# Input_Digital.net
KiCad netlist of a schematic drawn in Altium Designer
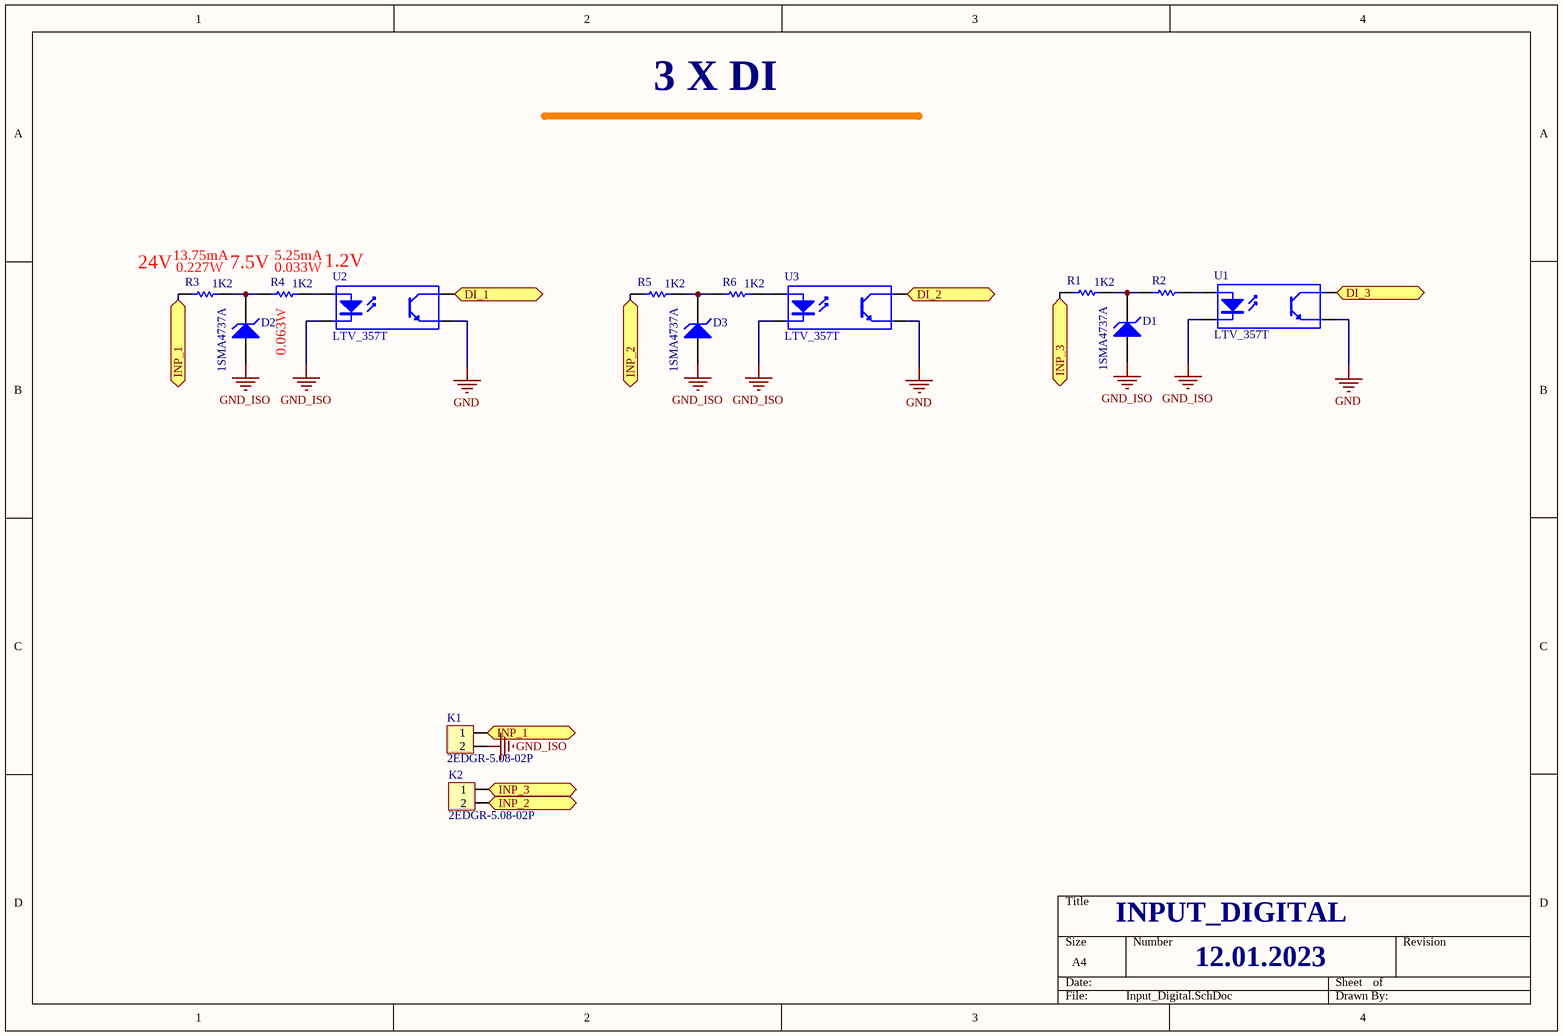
[diagram p0: Input_Digital.SchDoc]

(export (version "E")
  (design (tool "Eeschema 10.0.6"))
  (components
    (comp (ref "D1")
      (value "1SMA4737A")
      (footprint "DO214AC")
      (description "DIODE Zener Diode 7.5V 1W DO214AC")
      (fields (field (name "PUBLISHER") "Altium Limited"))
      (libsource (lib "geolib") (part "DIODE"))
    )
    (comp (ref "D2")
      (value "1SMA4737A")
      (footprint "DO214AC")
      (description "DIODE Zener Diode 7.5V 1W DO214AC")
      (fields (field (name "PUBLISHER") "Altium Limited"))
      (libsource (lib "geolib") (part "DIODE"))
    )
    (comp (ref "D3")
      (value "1SMA4737A")
      (footprint "DO214AC")
      (description "DIODE Zener Diode 7.5V 1W DO214AC")
      (fields (field (name "PUBLISHER") "Altium Limited"))
      (libsource (lib "geolib") (part "DIODE"))
    )
    (comp (ref "K1")
      (value "2EDGR-5.08-02P")
      (footprint "CON_DG129_02P")
      (description "CONNECTOR 5.08mm 2PIN 90DEG")
      (libsource (lib "geolib") (part "KLEMENS_2P"))
    )
    (comp (ref "K2")
      (value "2EDGR-5.08-02P")
      (footprint "CON_DG129_02P")
      (description "CONNECTOR 5.08mm 2PIN 90DEG")
      (libsource (lib "geolib") (part "KLEMENS_2P"))
    )
    (comp (ref "R1")
      (value "1K2")
      (footprint "RES3216[1206]")
      (description "RESISTOR 1206 Case %1")
      (fields (field (name "PUBLISHER") "Altium Limited"))
      (libsource (lib "geolib") (part "RES"))
    )
    (comp (ref "R2")
      (value "1K2")
      (footprint "RES2012[0805]")
      (description "RESISTOR 0805 Case %1")
      (fields (field (name "PUBLISHER") "Altium Limited"))
      (libsource (lib "geolib") (part "RES"))
    )
    (comp (ref "R3")
      (value "1K2")
      (footprint "RES3216[1206]")
      (description "RESISTOR 1206 Case %1")
      (fields (field (name "PUBLISHER") "Altium Limited"))
      (libsource (lib "geolib") (part "RES"))
    )
    (comp (ref "R4")
      (value "1K2")
      (footprint "RES2012[0805]")
      (description "RESISTOR 0805 Case %1")
      (fields (field (name "PUBLISHER") "Altium Limited"))
      (libsource (lib "geolib") (part "RES"))
    )
    (comp (ref "R5")
      (value "1K2")
      (footprint "RES3216[1206]")
      (description "RESISTOR 1206 Case %1")
      (fields (field (name "PUBLISHER") "Altium Limited"))
      (libsource (lib "geolib") (part "RES"))
    )
    (comp (ref "R6")
      (value "1K2")
      (footprint "RES2012[0805]")
      (description "RESISTOR 0805 Case %1")
      (fields (field (name "PUBLISHER") "Altium Limited"))
      (libsource (lib "geolib") (part "RES"))
    )
    (comp (ref "U1")
      (value "LTV_357T")
      (footprint "SMD-4")
      (description "OPTOCOUPLER Transistor Output Optocouplers Optocoupler Phototrans")
      (fields (field (name "PUBLISHER") "Altium Limited"))
      (libsource (lib "geolib") (part "LVT_357T"))
    )
    (comp (ref "U2")
      (value "LTV_357T")
      (footprint "SMD-4")
      (description "OPTOCOUPLER Transistor Output Optocouplers Optocoupler Phototrans")
      (fields (field (name "PUBLISHER") "Altium Limited"))
      (libsource (lib "geolib") (part "LVT_357T"))
    )
    (comp (ref "U3")
      (value "LTV_357T")
      (footprint "SMD-4")
      (description "OPTOCOUPLER Transistor Output Optocouplers Optocoupler Phototrans")
      (fields (field (name "PUBLISHER") "Altium Limited"))
      (libsource (lib "geolib") (part "LVT_357T"))
    )
  )
  (nets
    (net (code "1") (name "/DI_1") (class "Default")
      (node (ref "U2") (pin "4") (pinfunction "C_4") (pintype "passive"))
    )
    (net (code "2") (name "/DI_2") (class "Default")
      (node (ref "U3") (pin "4") (pinfunction "C_4") (pintype "passive"))
    )
    (net (code "3") (name "/DI_3") (class "Default")
      (node (ref "U1") (pin "4") (pinfunction "C_4") (pintype "passive"))
    )
    (net (code "4") (name "/INP_1") (class "Default")
      (node (ref "K1") (pin "1") (pinfunction "1_1") (pintype "passive"))
      (node (ref "R3") (pin "2") (pinfunction "2_2") (pintype "passive"))
    )
    (net (code "5") (name "/INP_2") (class "Default")
      (node (ref "K2") (pin "2") (pinfunction "2_2") (pintype "passive"))
      (node (ref "R5") (pin "2") (pinfunction "2_2") (pintype "passive"))
    )
    (net (code "6") (name "/INP_3") (class "Default")
      (node (ref "K2") (pin "1") (pinfunction "1_1") (pintype "passive"))
      (node (ref "R1") (pin "2") (pinfunction "2_2") (pintype "passive"))
    )
    (net (code "7") (name "GND") (class "Default")
      (node (ref "U1") (pin "3") (pinfunction "E_3") (pintype "passive"))
      (node (ref "U2") (pin "3") (pinfunction "E_3") (pintype "passive"))
      (node (ref "U3") (pin "3") (pinfunction "E_3") (pintype "passive"))
    )
    (net (code "8") (name "GND_ISO") (class "Default")
      (node (ref "D1") (pin "1") (pinfunction "A_1") (pintype "passive"))
      (node (ref "D2") (pin "1") (pinfunction "A_1") (pintype "passive"))
      (node (ref "D3") (pin "1") (pinfunction "A_1") (pintype "passive"))
      (node (ref "K1") (pin "2") (pinfunction "2_2") (pintype "passive"))
      (node (ref "U1") (pin "2") (pinfunction "K_2") (pintype "passive"))
      (node (ref "U2") (pin "2") (pinfunction "K_2") (pintype "passive"))
      (node (ref "U3") (pin "2") (pinfunction "K_2") (pintype "passive"))
    )
    (net (code "9") (name "Net-(D1-K)") (class "Default")
      (node (ref "D1") (pin "2") (pinfunction "K_2") (pintype "passive"))
      (node (ref "R1") (pin "1") (pinfunction "1_1") (pintype "passive"))
      (node (ref "R2") (pin "2") (pinfunction "2_2") (pintype "passive"))
    )
    (net (code "10") (name "Net-(D2-K)") (class "Default")
      (node (ref "D2") (pin "2") (pinfunction "K_2") (pintype "passive"))
      (node (ref "R3") (pin "1") (pinfunction "1_1") (pintype "passive"))
      (node (ref "R4") (pin "2") (pinfunction "2_2") (pintype "passive"))
    )
    (net (code "11") (name "Net-(D3-K)") (class "Default")
      (node (ref "D3") (pin "2") (pinfunction "K_2") (pintype "passive"))
      (node (ref "R5") (pin "1") (pinfunction "1_1") (pintype "passive"))
      (node (ref "R6") (pin "2") (pinfunction "2_2") (pintype "passive"))
    )
    (net (code "12") (name "Net-(U1-A)") (class "Default")
      (node (ref "R2") (pin "1") (pinfunction "1_1") (pintype "passive"))
      (node (ref "U1") (pin "1") (pinfunction "A_1") (pintype "passive"))
    )
    (net (code "13") (name "Net-(U2-A)") (class "Default")
      (node (ref "R4") (pin "1") (pinfunction "1_1") (pintype "passive"))
      (node (ref "U2") (pin "1") (pinfunction "A_1") (pintype "passive"))
    )
    (net (code "14") (name "Net-(U3-A)") (class "Default")
      (node (ref "R6") (pin "1") (pinfunction "1_1") (pintype "passive"))
      (node (ref "U3") (pin "1") (pinfunction "A_1") (pintype "passive"))
    )
  )
)
